# TSAL_REV1_1.net
KiCad netlist of a schematic drawn in Altium Designer
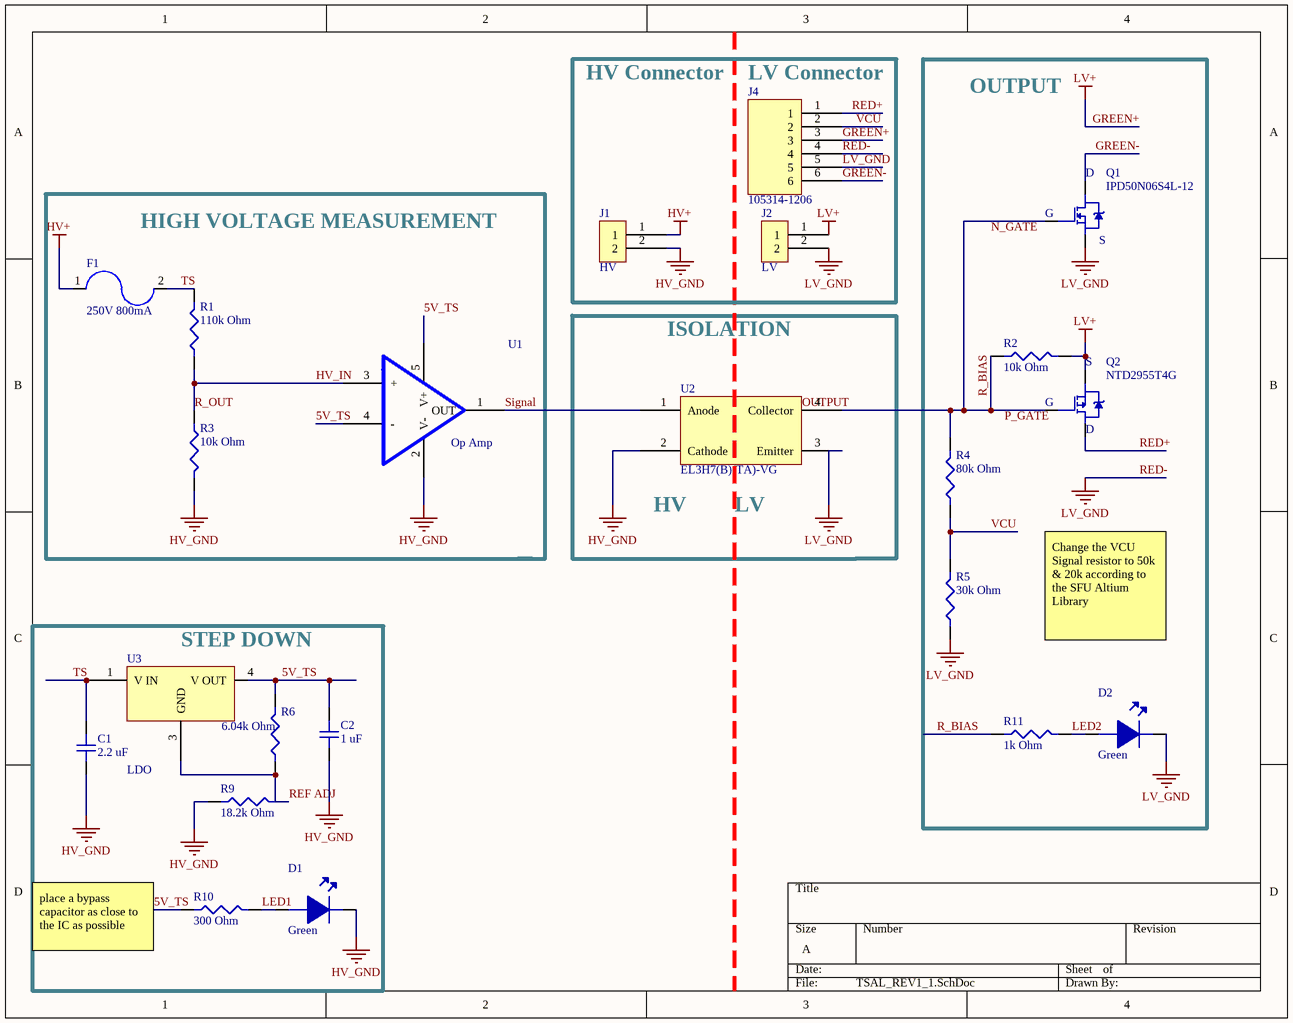
[diagram p0: TSAL_REV1_1.SchDoc]

(export (version "E")
  (design (tool "Eeschema 10.0.6"))
  (components
    (comp (ref "C1")
      (value "2.2 uF")
      (footprint "CAPC5850X25N")
      (description "CAP CER 2.2UF 250V X7T 2220")
      (fields
        (field (name "MANUFACTURER") "TDK")
        (field (name "MANUFACTURER PART NUMBER") "CGA9P3X7T2E225K250KE")
      )
      (libsource (lib "TSAL_REV1") (part "CGA9P3X7T2E225K250KE"))
    )
    (comp (ref "C2")
      (value "1 uF")
      (description "Cap Ceramic 1uF 10V X5R 10% SMD 0603 85C Paper T/R")
      (fields
        (field (name "MANUFACTURER") "Samsung")
        (field (name "MANUFACTURER PART NUMBER") "CL10A105KP8NNNC")
      )
      (libsource (lib "TSAL_REV1") (part "CL10A105KP8NNNC"))
    )
    (comp (ref "D1")
      (value "Green")
      (footprint "LED_0603")
      (description "LED Uni-Color Green 574nm 2-Pin Chip LED T/R")
      (fields
        (field (name "MANUFACTURER") "Vishay Lite-On")
        (field (name "MANUFACTURER PART NUMBER") "LTST-C191KGKT")
      )
      (libsource (lib "TSAL_REV1") (part "LTST-C191KGKT"))
    )
    (comp (ref "D2")
      (value "Green")
      (footprint "LED_0603")
      (description "LED Uni-Color Green 574nm 2-Pin Chip LED T/R")
      (fields
        (field (name "MANUFACTURER") "Vishay Lite-On")
        (field (name "MANUFACTURER PART NUMBER") "LTST-C191KGKT")
      )
      (libsource (lib "TSAL_REV1") (part "LTST-C191KGKT"))
    )
    (comp (ref "F1")
      (value "250V 800mA")
      (footprint "FUSE_SMD")
      (fields (field (name "MANUFACTURER") "Bel") (field (name "MANUFACTURER PART NUMBER") "0678D0800-02"))
      (libsource (lib "TSAL_REV1") (part "0678D0800-02"))
    )
    (comp (ref "J1")
      (value "HV")
      (footprint "2_PIN_CONNECTOR")
      (fields (field (name "MANUFACTURER") "Molex") (field (name "MANUFACTURER PART NUMBER") "0705530001"))
      (libsource (lib "TSAL_REV1") (part "0705530001"))
    )
    (comp (ref "J2")
      (value "LV")
      (footprint "2_PIN_CONNECTOR")
      (fields (field (name "MANUFACTURER") "Molex") (field (name "MANUFACTURER PART NUMBER") "0705530001"))
      (libsource (lib "TSAL_REV1") (part "0705530001"))
    )
    (comp (ref "J4")
      (value "105314-1206")
      (footprint "*MOLEX_1053141206")
      (description "CONN HEADER R/A 6POS 2.5MM")
      (fields (field (name "MANUFACTURER") "Molex"))
      (libsource (lib "TSAL_REV1") (part "105314-1206"))
    )
    (comp (ref "Q1")
      (value "IPD50N06S4L-12")
      (footprint "DPAK228P998X235-3N")
      (description "MOSFET N-CH 60V 50A TO252-3-11")
      (fields (field (name "MANUFACTURER") "Infineon"))
      (libsource (lib "TSAL_REV1") (part "IPD50N06S4L-12"))
    )
    (comp (ref "Q2")
      (value "NTD2955T4G")
      (footprint "DPAK228P991X238-3N")
      (description "Trans MOSFET P-CH 60V 12A 3-Pin(2+Tab) DPAK T/R")
      (fields (field (name "MANUFACTURER") "ON Semiconductor"))
      (libsource (lib "TSAL_REV1") (part "NTD2955T4G"))
    )
    (comp (ref "R1")
      (value "110k Ohm")
      (footprint "RESC3116X06N")
      (description "RES SMD 110K OHM 1% 1/4W 1206")
      (fields
        (field (name "MANUFACTURER") "Yageo")
        (field (name "MANUFACTURER PART NUMBER") "RC1206FR-07110KL")
      )
      (libsource (lib "TSAL_REV1") (part "RC1206FR-07110KL"))
    )
    (comp (ref "R2")
      (value "10k Ohm")
      (footprint "RESC2012X06N")
      (description "RES 10K OHM 1% 1/4W 0805")
      (fields
        (field (name "MANUFACTURER") "Stackpole Electronics")
        (field (name "MANUFACTURER PART NUMBER") "RNCP0805FTD10K0")
      )
      (libsource (lib "TSAL_REV1") (part "RNCP0805FTD10K0"))
    )
    (comp (ref "R3")
      (value "10k Ohm")
      (footprint "RESC2012X06N")
      (description "RES 10K OHM 1% 1/4W 0805")
      (fields
        (field (name "MANUFACTURER") "Stackpole Electronics")
        (field (name "MANUFACTURER PART NUMBER") "RNCP0805FTD10K0")
      )
      (libsource (lib "TSAL_REV1") (part "RNCP0805FTD10K0"))
    )
    (comp (ref "R4")
      (value "80k Ohm")
      (footprint "RESC1608X06N")
      (description "RES 80K OHM 0.1% 0.15W 0603")
      (fields
        (field (name "MANUFACTURER") "Vishay Dale")
        (field (name "MANUFACTURER PART NUMBER") "PTN0603E8002BST1")
      )
      (libsource (lib "TSAL_REV1") (part "PTN0603E8002BST1"))
    )
    (comp (ref "R5")
      (value "30k Ohm")
      (footprint "RESC2012X06N")
      (description "Thick Film Resistors CRG0805 1% 30K")
      (fields
        (field (name "MANUFACTURER") "TE Connectivity")
        (field (name "MANUFACTURER PART NUMBER") "CRG0805F30K")
      )
      (libsource (lib "TSAL_REV1") (part "CRG0805F30K"))
    )
    (comp (ref "R6")
      (value "6.04k Ohm")
      (footprint "RESC2012X06N")
      (description "RES SMD 6.04KOHM 0.5% 1/10W 0805")
      (fields
        (field (name "MANUFACTURER") "Susumu")
        (field (name "MANUFACTURER PART NUMBER") "RR1220P-6041-D-M")
      )
      (libsource (lib "TSAL_REV1") (part "RR1220P-6041-D-M"))
    )
    (comp (ref "R9")
      (value "18.2k Ohm")
      (footprint "RESC2012X06N")
      (description "Panasonic ERA Series Thin Film Surface Mount Resistor 0805 Case 18.2k 0.1% 0.125W 25ppm/C")
      (fields
        (field (name "MANUFACTURER") "Panasonic")
        (field (name "MANUFACTURER PART NUMBER") "ERA-6AEB1822V")
      )
      (libsource (lib "TSAL_REV1") (part "ERA-6AEB1822V"))
    )
    (comp (ref "R10")
      (value "300 Ohm")
      (footprint "RESC1608X06N")
      (description "RES SMD 300 OHM 0.5% 1/16W 0603")
      (fields
        (field (name "MANUFACTURER") "Susumu")
        (field (name "MANUFACTURER PART NUMBER") "RR0816P-301-D")
      )
      (libsource (lib "TSAL_REV1") (part "RR0816P-301-D"))
    )
    (comp (ref "R11")
      (value "1k Ohm")
      (footprint "RESC1608X06N")
      (description "RES SMD 1K OHM 5% 1/10W 0603")
      (fields
        (field (name "MANUFACTURER") "Yageo")
        (field (name "MANUFACTURER PART NUMBER") "RC0603JR-071KL")
      )
      (libsource (lib "TSAL_REV1") (part "RC0603JR-071KL"))
    )
    (comp (ref "U1")
      (value "Op Amp")
      (footprint "SOT95P280X145-5N")
      (description "MICROCHIP - MCP6001T-I/OT - OP AMP, 1MHZ, 0.6V/uS, SOT-23-5, FULL REEL")
      (fields
        (field (name "MANUFACTURER") "Microchip")
        (field (name "MANUFACTURER PART NUMBER") "MCP6001T-I/OT")
      )
      (libsource (lib "TSAL_REV1_1_SchematicLib ") (part "MCP6001T-I/OT"))
    )
    (comp (ref "U2")
      (value "EL3H7(B)(TA)-VG")
      (footprint "SOIC127P700X200-4N")
      (description "OPTOISOLATOR 3.75KV TRANS 4-SSOP")
      (fields (field (name "MANUFACTURER") "Everlight"))
      (libsource (lib "TSAL_REV1") (part "EL3H7(B)(TA)-VG"))
    )
    (comp (ref "U3")
      (value "LDO")
      (footprint "DPAK228P998X235-3N")
      (description "Standard Regulator Pos 1.2V to 440V 0.01A 3-Pin(2+Tab) TO-252")
      (fields (field (name "MANUFACTURER") "Microchip") (field (name "MANUFACTURER PART NUMBER") "LR8K4-G"))
      (libsource (lib "TSAL_REV1") (part "LR8K4-G"))
    )
  )
  (nets
    (net (code "1") (name "/5V_TS") (class "Default")
      (node (ref "C2") (pin "2") (pinfunction "2_2") (pintype "passive"))
      (node (ref "R10") (pin "1") (pinfunction "1_1") (pintype "passive"))
      (node (ref "R6") (pin "2") (pinfunction "2_2") (pintype "passive"))
      (node (ref "U1") (pin "4") (pinfunction "-_4") (pintype "passive"))
      (node (ref "U1") (pin "5") (pinfunction "V+_5") (pintype "passive"))
      (node (ref "U3") (pin "4") (pinfunction "V_OUT_4") (pintype "passive"))
    )
    (net (code "2") (name "/GREEN-") (class "Default")
      (node (ref "J4") (pin "6") (pinfunction "6_6") (pintype "passive"))
      (node (ref "Q1") (pin "4") (pinfunction "4_4") (pintype "passive"))
    )
    (net (code "3") (name "/HV_IN") (class "Default")
      (node (ref "R1") (pin "1") (pinfunction "1_1") (pintype "passive"))
      (node (ref "R3") (pin "1") (pinfunction "1_1") (pintype "passive"))
      (node (ref "U1") (pin "3") (pinfunction "+_3") (pintype "passive"))
    )
    (net (code "4") (name "/LED1") (class "Default")
      (node (ref "D1") (pin "1") (pinfunction "1_1") (pintype "passive"))
      (node (ref "R10") (pin "2") (pinfunction "2_2") (pintype "passive"))
    )
    (net (code "5") (name "/LED2") (class "Default")
      (node (ref "D2") (pin "1") (pinfunction "1_1") (pintype "passive"))
      (node (ref "R11") (pin "2") (pinfunction "2_2") (pintype "passive"))
    )
    (net (code "9") (name "/RED+") (class "Default")
      (node (ref "J4") (pin "1") (pinfunction "1_1") (pintype "passive"))
      (node (ref "Q2") (pin "3") (pinfunction "3_3") (pintype "passive"))
    )
    (net (code "10") (name "/REF ADJ") (class "Default")
      (node (ref "R6") (pin "1") (pinfunction "1_1") (pintype "passive"))
      (node (ref "R9") (pin "2") (pinfunction "2_2") (pintype "passive"))
      (node (ref "U3") (pin "3") (pinfunction "GND_3") (pintype "passive"))
    )
    (net (code "11") (name "/R_BIAS") (class "Default")
      (node (ref "Q1") (pin "1") (pinfunction "1_1") (pintype "passive"))
      (node (ref "Q2") (pin "1") (pinfunction "1_1") (pintype "passive"))
      (node (ref "R11") (pin "1") (pinfunction "1_1") (pintype "passive"))
      (node (ref "R2") (pin "1") (pinfunction "1_1") (pintype "passive"))
      (node (ref "R4") (pin "2") (pinfunction "2_2") (pintype "passive"))
      (node (ref "U2") (pin "4") (pinfunction "Collector_4") (pintype "passive"))
    )
    (net (code "12") (name "/Signal") (class "Default")
      (node (ref "U1") (pin "1") (pinfunction "OUT_1") (pintype "passive"))
      (node (ref "U2") (pin "1") (pinfunction "Anode_1") (pintype "passive"))
    )
    (net (code "13") (name "/TS") (class "Default")
      (node (ref "C1") (pin "2") (pinfunction "2_2") (pintype "passive"))
      (node (ref "F1") (pin "2") (pinfunction "2_2") (pintype "passive"))
      (node (ref "R1") (pin "2") (pinfunction "2_2") (pintype "passive"))
      (node (ref "U3") (pin "1") (pinfunction "V_IN_1") (pintype "passive"))
    )
    (net (code "14") (name "/VCU") (class "Default")
      (node (ref "J4") (pin "2") (pinfunction "2_2") (pintype "passive"))
      (node (ref "R4") (pin "1") (pinfunction "1_1") (pintype "passive"))
      (node (ref "R5") (pin "2") (pinfunction "2_2") (pintype "passive"))
    )
    (net (code "15") (name "HV+") (class "Default")
      (node (ref "F1") (pin "1") (pinfunction "1_1") (pintype "passive"))
      (node (ref "J1") (pin "1") (pinfunction "1_1") (pintype "passive"))
    )
    (net (code "16") (name "HV_GND") (class "Default")
      (node (ref "C1") (pin "1") (pinfunction "1_1") (pintype "passive"))
      (node (ref "C2") (pin "1") (pinfunction "1_1") (pintype "passive"))
      (node (ref "D1") (pin "2") (pinfunction "2_2") (pintype "passive"))
      (node (ref "J1") (pin "2") (pinfunction "2_2") (pintype "passive"))
      (node (ref "R3") (pin "2") (pinfunction "2_2") (pintype "passive"))
      (node (ref "R9") (pin "1") (pinfunction "1_1") (pintype "passive"))
      (node (ref "U1") (pin "2") (pinfunction "V-_2") (pintype "passive"))
      (node (ref "U2") (pin "2") (pinfunction "Cathode_2") (pintype "passive"))
    )
    (net (code "17") (name "LV+") (class "Default")
      (node (ref "J2") (pin "1") (pinfunction "1_1") (pintype "passive"))
      (node (ref "J4") (pin "3") (pinfunction "3_3") (pintype "passive"))
      (node (ref "Q2") (pin "4") (pinfunction "4_4") (pintype "passive"))
      (node (ref "R2") (pin "2") (pinfunction "2_2") (pintype "passive"))
    )
    (net (code "18") (name "LV_GND") (class "Default")
      (node (ref "D2") (pin "2") (pinfunction "2_2") (pintype "passive"))
      (node (ref "J2") (pin "2") (pinfunction "2_2") (pintype "passive"))
      (node (ref "J4") (pin "4") (pinfunction "4_4") (pintype "passive"))
      (node (ref "J4") (pin "5") (pinfunction "5_5") (pintype "passive"))
      (node (ref "Q1") (pin "3") (pinfunction "3_3") (pintype "passive"))
      (node (ref "R5") (pin "1") (pinfunction "1_1") (pintype "passive"))
      (node (ref "U2") (pin "3") (pinfunction "Emitter_3") (pintype "passive"))
    )
  )
)
